# Glasses-LEDBoard.net
KiCad netlist of a schematic drawn in Altium Designer
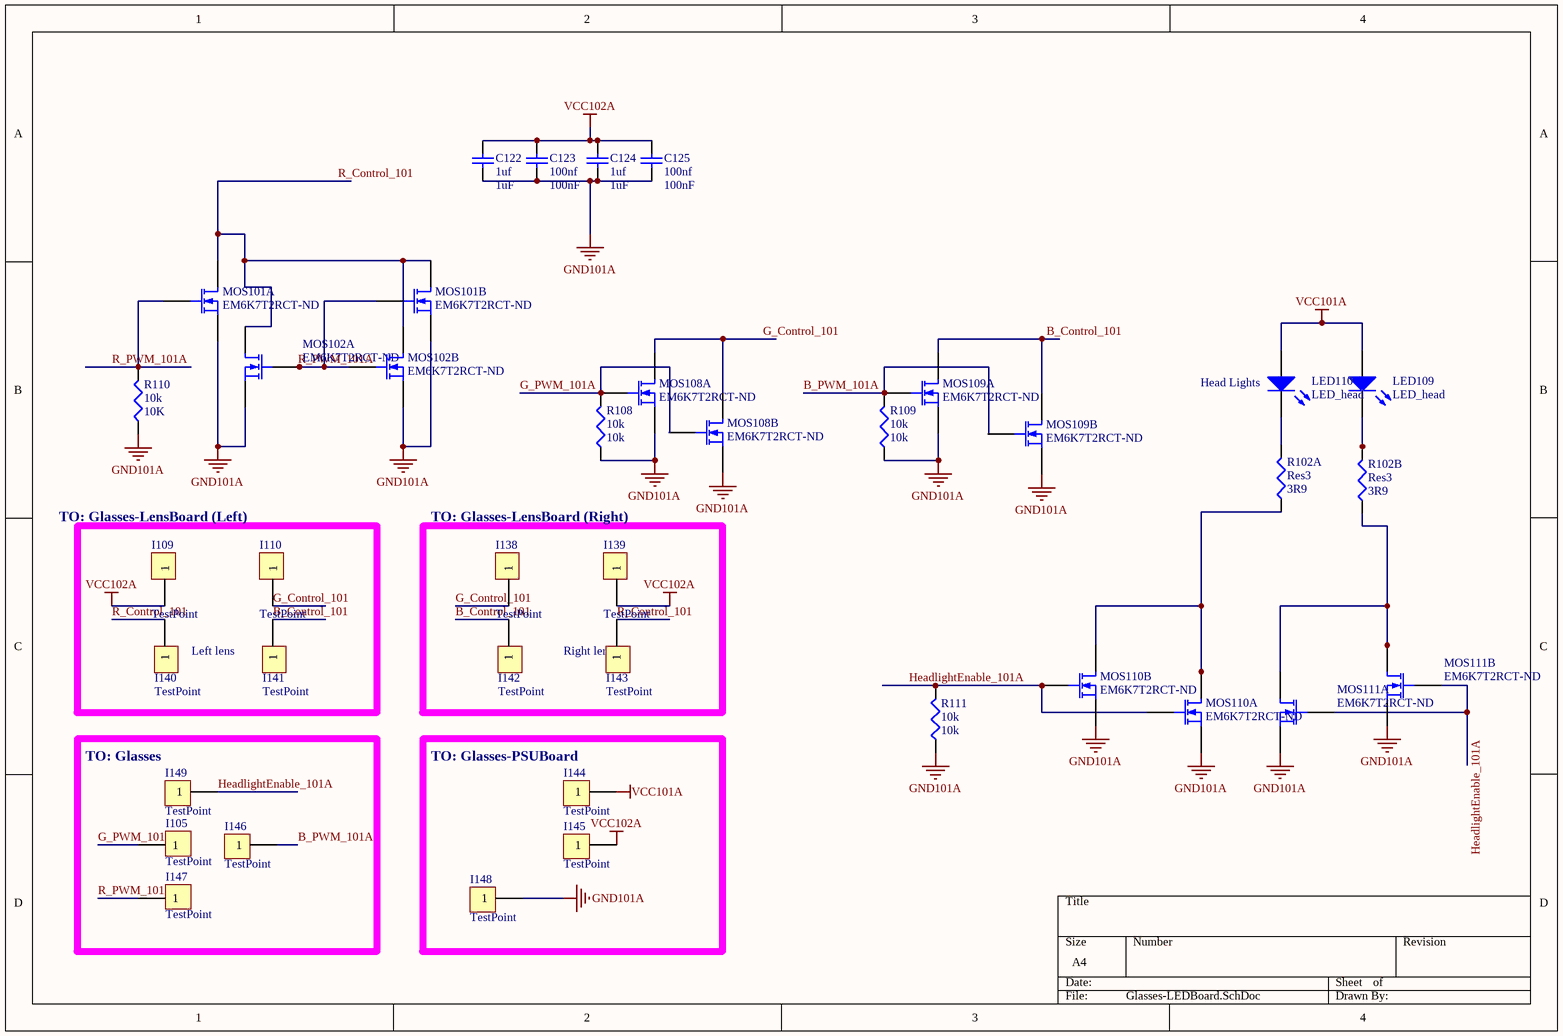
[diagram p0: Glasses-LEDBoard.SchDoc]

(export (version "E")
  (design (tool "Eeschema 10.0.6"))
  (components
    (comp (ref "C122")
      (value "1uf")
      (footprint "0603")
      (description "Capacitor (Semiconductor SIM Model)")
      (fields (field (name "ALTIUM_VALUE") "1uF") (field (name "PUBLISHER") "Altium Limited"))
      (libsource (lib "Miscellaneous Devices") (part "Cap Semi"))
    )
    (comp (ref "C123")
      (value "100nf")
      (footprint "0603")
      (description "Capacitor (Semiconductor SIM Model)")
      (fields (field (name "ALTIUM_VALUE") "100nF") (field (name "PUBLISHER") "Altium Limited"))
      (libsource (lib "Miscellaneous Devices") (part "Cap Semi"))
    )
    (comp (ref "C124")
      (value "1uf")
      (footprint "0603")
      (description "Capacitor (Semiconductor SIM Model)")
      (fields (field (name "ALTIUM_VALUE") "1uF") (field (name "PUBLISHER") "Altium Limited"))
      (libsource (lib "Miscellaneous Devices") (part "Cap Semi"))
    )
    (comp (ref "C125")
      (value "100nf")
      (footprint "0603")
      (description "Capacitor (Semiconductor SIM Model)")
      (fields (field (name "ALTIUM_VALUE") "100nF") (field (name "PUBLISHER") "Altium Limited"))
      (libsource (lib "Miscellaneous Devices") (part "Cap Semi"))
    )
    (comp (ref "I105") (value "TestPoint") (footprint "TestPoint") (libsource (lib "") (part "TestPoint_3")))
    (comp (ref "I109") (value "TestPoint") (footprint "TestPoint") (libsource (lib "") (part "TestPoint_2")))
    (comp (ref "I110") (value "TestPoint") (footprint "TestPoint") (libsource (lib "") (part "TestPoint_2")))
    (comp (ref "I138") (value "TestPoint") (footprint "TestPoint") (libsource (lib "") (part "TestPoint_2")))
    (comp (ref "I139") (value "TestPoint") (footprint "TestPoint") (libsource (lib "") (part "TestPoint_2")))
    (comp (ref "I140")
      (value "TestPoint")
      (footprint "TestPoint")
      (libsource (lib "Schlib1") (part "TestPoint"))
    )
    (comp (ref "I141")
      (value "TestPoint")
      (footprint "TestPoint")
      (libsource (lib "Schlib1") (part "TestPoint"))
    )
    (comp (ref "I142")
      (value "TestPoint")
      (footprint "TestPoint")
      (libsource (lib "Schlib1") (part "TestPoint"))
    )
    (comp (ref "I143")
      (value "TestPoint")
      (footprint "TestPoint")
      (libsource (lib "Schlib1") (part "TestPoint"))
    )
    (comp (ref "I144") (value "TestPoint") (footprint "TestPoint") (libsource (lib "") (part "TestPoint_1")))
    (comp (ref "I145") (value "TestPoint") (footprint "TestPoint") (libsource (lib "") (part "TestPoint_1")))
    (comp (ref "I146") (value "TestPoint") (footprint "TestPoint") (libsource (lib "") (part "TestPoint_1")))
    (comp (ref "I147") (value "TestPoint") (footprint "TestPoint") (libsource (lib "") (part "TestPoint_3")))
    (comp (ref "I148") (value "TestPoint") (footprint "TestPoint") (libsource (lib "") (part "TestPoint_1")))
    (comp (ref "I149") (value "TestPoint") (footprint "TestPoint") (libsource (lib "") (part "TestPoint_1")))
    (comp (ref "LED109")
      (value "LED_head")
      (footprint "LED Headlamp")
      (description "Typical INFRARED GaAs LED")
      (fields (field (name "PUBLISHER") "Altium Limited"))
      (libsource (lib "Miscellaneous Devices") (part "LED0"))
    )
    (comp (ref "LED110")
      (value "LED_head")
      (footprint "LED Headlamp")
      (description "Typical INFRARED GaAs LED")
      (fields (field (name "PUBLISHER") "Altium Limited"))
      (libsource (lib "Miscellaneous Devices") (part "LED0"))
    )
    (comp (ref "MOS101")
      (value "EM6K7T2RCT-ND")
      (footprint "EM6K7T2R-EMT6")
      (libsource (lib "Schlib1") (part "EM6K7T2RCT-ND"))
    )
    (comp (ref "MOS102")
      (value "EM6K7T2RCT-ND")
      (footprint "EM6K7T2R-EMT6")
      (libsource (lib "Schlib1") (part "EM6K7T2RCT-ND"))
    )
    (comp (ref "MOS108")
      (value "EM6K7T2RCT-ND")
      (footprint "EM6K7T2R-EMT6")
      (libsource (lib "Schlib1") (part "EM6K7T2RCT-ND"))
    )
    (comp (ref "MOS109")
      (value "EM6K7T2RCT-ND")
      (footprint "EM6K7T2R-EMT6")
      (libsource (lib "Schlib1") (part "EM6K7T2RCT-ND"))
    )
    (comp (ref "MOS110")
      (value "EM6K7T2RCT-ND")
      (footprint "EM6K7T2R-EMT6")
      (libsource (lib "Schlib1") (part "EM6K7T2RCT-ND"))
    )
    (comp (ref "MOS111")
      (value "EM6K7T2RCT-ND")
      (footprint "EM6K7T2R-EMT6")
      (libsource (lib "Schlib1") (part "EM6K7T2RCT-ND"))
    )
    (comp (ref "R102A")
      (value "Res3")
      (footprint "0805")
      (description "Resistor")
      (fields (field (name "ALTIUM_VALUE") "3R9") (field (name "PUBLISHER") "Altium Limited"))
      (libsource (lib "Miscellaneous Devices") (part "Res3"))
    )
    (comp (ref "R102B")
      (value "Res3")
      (footprint "0805")
      (description "Resistor")
      (fields (field (name "ALTIUM_VALUE") "3R9") (field (name "PUBLISHER") "Altium Limited"))
      (libsource (lib "Miscellaneous Devices") (part "Res3"))
    )
    (comp (ref "R108")
      (value "10k")
      (footprint "0603")
      (description "Resistor")
      (fields (field (name "ALTIUM_VALUE") "10k") (field (name "PUBLISHER") "Altium Limited"))
      (libsource (lib "Miscellaneous Devices") (part "Res3"))
    )
    (comp (ref "R109")
      (value "10k")
      (footprint "0603")
      (description "Resistor")
      (fields (field (name "ALTIUM_VALUE") "10k") (field (name "PUBLISHER") "Altium Limited"))
      (libsource (lib "Miscellaneous Devices") (part "Res3"))
    )
    (comp (ref "R110")
      (value "10k")
      (footprint "0603")
      (description "Resistor")
      (fields (field (name "ALTIUM_VALUE") "10K") (field (name "PUBLISHER") "Altium Limited"))
      (libsource (lib "Miscellaneous Devices") (part "Res3"))
    )
    (comp (ref "R111")
      (value "10k")
      (footprint "0603")
      (description "Resistor")
      (fields (field (name "ALTIUM_VALUE") "10k") (field (name "PUBLISHER") "Altium Limited"))
      (libsource (lib "Miscellaneous Devices") (part "Res3"))
    )
  )
  (nets
    (net (code "1") (name "/B_Control_101") (class "Default")
      (node (ref "I141") (pin "1") (pinfunction "1_1") (pintype "passive"))
      (node (ref "I142") (pin "1") (pinfunction "1_1") (pintype "passive"))
      (node (ref "MOS109") (pin "3") (pinfunction "D_3") (pintype "passive"))
      (node (ref "MOS109") (pin "6") (pinfunction "D_6") (pintype "passive"))
    )
    (net (code "2") (name "/B_PWM_101A") (class "Default")
      (node (ref "I146") (pin "1") (pinfunction "1_1") (pintype "passive"))
      (node (ref "MOS109") (pin "2") (pinfunction "G_2") (pintype "passive"))
      (node (ref "MOS109") (pin "5") (pinfunction "G_5") (pintype "passive"))
      (node (ref "R109") (pin "2") (pinfunction "2_2") (pintype "passive"))
    )
    (net (code "3") (name "/G_Control_101") (class "Default")
      (node (ref "I110") (pin "1") (pinfunction "1_1") (pintype "passive"))
      (node (ref "I138") (pin "1") (pinfunction "1_1") (pintype "passive"))
      (node (ref "MOS108") (pin "3") (pinfunction "D_3") (pintype "passive"))
      (node (ref "MOS108") (pin "6") (pinfunction "D_6") (pintype "passive"))
    )
    (net (code "4") (name "/G_PWM_101A") (class "Default")
      (node (ref "I105") (pin "1") (pinfunction "1_1") (pintype "passive"))
      (node (ref "MOS108") (pin "2") (pinfunction "G_2") (pintype "passive"))
      (node (ref "MOS108") (pin "5") (pinfunction "G_5") (pintype "passive"))
      (node (ref "R108") (pin "2") (pinfunction "2_2") (pintype "passive"))
    )
    (net (code "5") (name "/HeadlightEnable_101A") (class "Default")
      (node (ref "I149") (pin "1") (pinfunction "1_1") (pintype "passive"))
      (node (ref "MOS110") (pin "2") (pinfunction "G_2") (pintype "passive"))
      (node (ref "MOS110") (pin "5") (pinfunction "G_5") (pintype "passive"))
      (node (ref "MOS111") (pin "2") (pinfunction "G_2") (pintype "passive"))
      (node (ref "MOS111") (pin "5") (pinfunction "G_5") (pintype "passive"))
      (node (ref "R111") (pin "2") (pinfunction "2_2") (pintype "passive"))
    )
    (net (code "6") (name "/R_Control_101") (class "Default")
      (node (ref "I140") (pin "1") (pinfunction "1_1") (pintype "passive"))
      (node (ref "I143") (pin "1") (pinfunction "1_1") (pintype "passive"))
      (node (ref "MOS101") (pin "3") (pinfunction "D_3") (pintype "passive"))
      (node (ref "MOS101") (pin "6") (pinfunction "D_6") (pintype "passive"))
      (node (ref "MOS102") (pin "3") (pinfunction "D_3") (pintype "passive"))
      (node (ref "MOS102") (pin "6") (pinfunction "D_6") (pintype "passive"))
    )
    (net (code "7") (name "/R_PWM_101A") (class "Default")
      (node (ref "I147") (pin "1") (pinfunction "1_1") (pintype "passive"))
      (node (ref "MOS101") (pin "2") (pinfunction "G_2") (pintype "passive"))
      (node (ref "MOS101") (pin "5") (pinfunction "G_5") (pintype "passive"))
      (node (ref "MOS102") (pin "2") (pinfunction "G_2") (pintype "passive"))
      (node (ref "MOS102") (pin "5") (pinfunction "G_5") (pintype "passive"))
      (node (ref "R110") (pin "2") (pinfunction "2_2") (pintype "passive"))
    )
    (net (code "8") (name "GND101A") (class "Default")
      (node (ref "C122") (pin "1") (pinfunction "1_1") (pintype "passive"))
      (node (ref "C123") (pin "1") (pinfunction "1_1") (pintype "passive"))
      (node (ref "C124") (pin "1") (pinfunction "1_1") (pintype "passive"))
      (node (ref "C125") (pin "1") (pinfunction "1_1") (pintype "passive"))
      (node (ref "I148") (pin "1") (pinfunction "1_1") (pintype "passive"))
      (node (ref "MOS101") (pin "1") (pinfunction "S_1") (pintype "passive"))
      (node (ref "MOS101") (pin "4") (pinfunction "S_4") (pintype "passive"))
      (node (ref "MOS102") (pin "1") (pinfunction "S_1") (pintype "passive"))
      (node (ref "MOS102") (pin "4") (pinfunction "S_4") (pintype "passive"))
      (node (ref "MOS108") (pin "1") (pinfunction "S_1") (pintype "passive"))
      (node (ref "MOS108") (pin "4") (pinfunction "S_4") (pintype "passive"))
      (node (ref "MOS109") (pin "1") (pinfunction "S_1") (pintype "passive"))
      (node (ref "MOS109") (pin "4") (pinfunction "S_4") (pintype "passive"))
      (node (ref "MOS110") (pin "1") (pinfunction "S_1") (pintype "passive"))
      (node (ref "MOS110") (pin "4") (pinfunction "S_4") (pintype "passive"))
      (node (ref "MOS111") (pin "1") (pinfunction "S_1") (pintype "passive"))
      (node (ref "MOS111") (pin "4") (pinfunction "S_4") (pintype "passive"))
      (node (ref "R108") (pin "1") (pinfunction "1_1") (pintype "passive"))
      (node (ref "R109") (pin "1") (pinfunction "1_1") (pintype "passive"))
      (node (ref "R110") (pin "1") (pinfunction "1_1") (pintype "passive"))
      (node (ref "R111") (pin "1") (pinfunction "1_1") (pintype "passive"))
    )
    (net (code "9") (name "Net-(LED109-K)") (class "Default")
      (node (ref "LED109") (pin "2") (pinfunction "K_2") (pintype "passive"))
      (node (ref "R102B") (pin "2") (pinfunction "2_2") (pintype "passive"))
    )
    (net (code "10") (name "Net-(LED110-K)") (class "Default")
      (node (ref "LED110") (pin "2") (pinfunction "K_2") (pintype "passive"))
      (node (ref "R102A") (pin "2") (pinfunction "2_2") (pintype "passive"))
    )
    (net (code "11") (name "Net-(MOS110A-D)") (class "Default")
      (node (ref "MOS110") (pin "3") (pinfunction "D_3") (pintype "passive"))
      (node (ref "MOS110") (pin "6") (pinfunction "D_6") (pintype "passive"))
      (node (ref "R102A") (pin "1") (pinfunction "1_1") (pintype "passive"))
    )
    (net (code "12") (name "Net-(MOS111A-D)") (class "Default")
      (node (ref "MOS111") (pin "3") (pinfunction "D_3") (pintype "passive"))
      (node (ref "MOS111") (pin "6") (pinfunction "D_6") (pintype "passive"))
      (node (ref "R102B") (pin "1") (pinfunction "1_1") (pintype "passive"))
    )
    (net (code "13") (name "VCC101A") (class "Default")
      (node (ref "I144") (pin "1") (pinfunction "1_1") (pintype "passive"))
      (node (ref "LED109") (pin "1") (pinfunction "A_1") (pintype "passive"))
      (node (ref "LED110") (pin "1") (pinfunction "A_1") (pintype "passive"))
    )
    (net (code "14") (name "VCC102A") (class "Default")
      (node (ref "C122") (pin "2") (pinfunction "2_2") (pintype "passive"))
      (node (ref "C123") (pin "2") (pinfunction "2_2") (pintype "passive"))
      (node (ref "C124") (pin "2") (pinfunction "2_2") (pintype "passive"))
      (node (ref "C125") (pin "2") (pinfunction "2_2") (pintype "passive"))
      (node (ref "I109") (pin "1") (pinfunction "1_1") (pintype "passive"))
      (node (ref "I139") (pin "1") (pinfunction "1_1") (pintype "passive"))
      (node (ref "I145") (pin "1") (pinfunction "1_1") (pintype "passive"))
    )
  )
)
